# Camera.net
KiCad netlist of a schematic drawn in Altium Designer
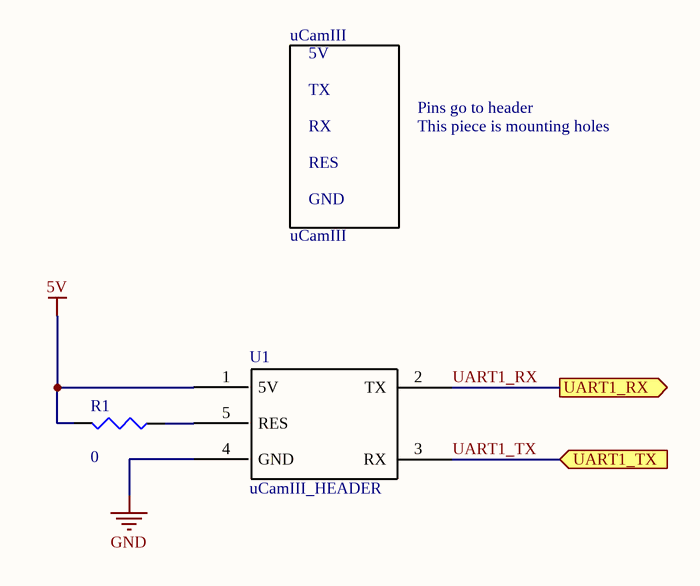
[diagram p0: Camera.SchDoc]

(export (version "E")
  (design (tool "Eeschema 10.0.6"))
  (components
    (comp (ref "R1")
      (value "0")
      (footprint "J1-0603")
      (description "Resistor")
      (fields (field (name "PUBLISHER") "Altium Limited"))
      (libsource (lib "Miscellaneous Devices") (part "Res3"))
    )
    (comp (ref "U1")
      (value "uCamIII_HEADER")
      (footprint "uCamIII_Header")
      (description "just a pin header for components")
      (libsource (lib "LowPower_3ER_Parts") (part "uCamIII_HEADER"))
    )
    (comp (ref "uCamIII")
      (value "uCamIII")
      (footprint "uCamIII")
      (libsource (lib "LowPower_3ER_Parts") (part "uCamIII"))
    )
  )
  (nets
    (net (code "1") (name "/UART1_RX") (class "Default")
      (node (ref "U1") (pin "2") (pinfunction "TX_2") (pintype "passive"))
    )
    (net (code "2") (name "/UART1_TX") (class "Default")
      (node (ref "U1") (pin "3") (pinfunction "RX_3") (pintype "passive"))
    )
    (net (code "3") (name "5V") (class "Default")
      (node (ref "R1") (pin "2") (pinfunction "2_2") (pintype "passive"))
      (node (ref "U1") (pin "1") (pinfunction "5V_1") (pintype "power_in"))
    )
    (net (code "4") (name "GND") (class "Default")
      (node (ref "U1") (pin "4") (pinfunction "GND_4") (pintype "power_in"))
    )
    (net (code "5") (name "Net-(U1-RES)") (class "Default")
      (node (ref "R1") (pin "1") (pinfunction "1_1") (pintype "passive"))
      (node (ref "U1") (pin "5") (pinfunction "RES_5") (pintype "passive"))
    )
  )
)
